# stepper-v1_1.net
KiCad netlist of a schematic drawn in EAGLE
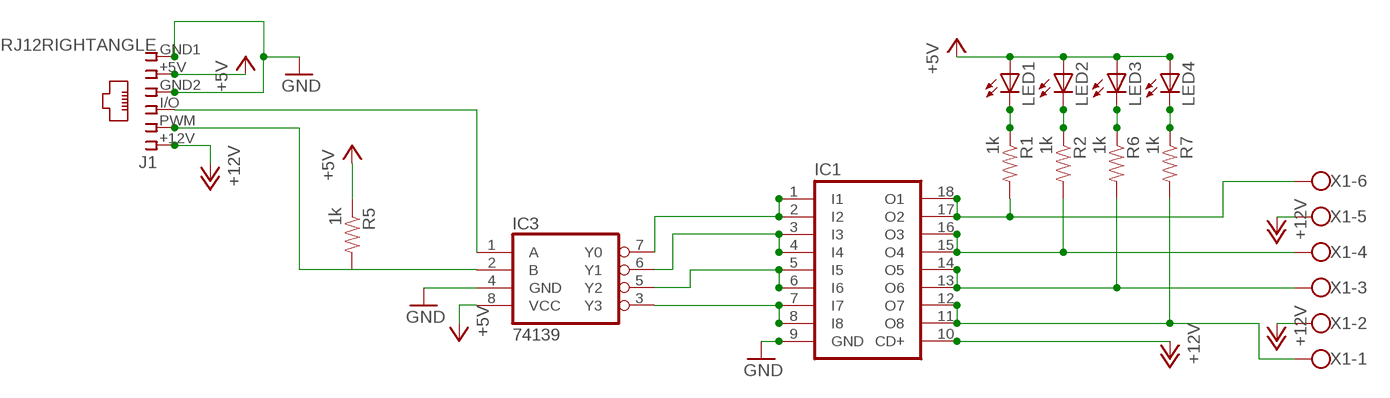
[diagram p0: schematic, sheet 1]

(export (version "E")
  (design (tool "Eeschema 10.0.6"))
  (components
    (comp (ref "IC1")
      (value "ULN2803A")
      (footprint "eagle-import:SO18W")
      (libsource (lib "eagle-import") (part "ULN2803A"))
    )
    (comp (ref "IC3")
      (value "74139")
      (footprint "eagle-import:SSOP08")
      (libsource (lib "eagle-import") (part "74139"))
    )
    (comp (ref "J1")
      (value "RJ12RIGHTANGLE")
      (footprint "eagle-import:RJ12-RIGHTANGLE")
      (libsource (lib "eagle-import") (part "RJ12RIGHTANGLE"))
    )
    (comp (ref "LED1")
      (value "LED3MM")
      (footprint "eagle-import:LED3MM")
      (libsource (lib "eagle-import") (part "LED3MM"))
    )
    (comp (ref "LED2")
      (value "LED3MM")
      (footprint "eagle-import:LED3MM")
      (libsource (lib "eagle-import") (part "LED3MM"))
    )
    (comp (ref "LED3")
      (value "LED3MM")
      (footprint "eagle-import:LED3MM")
      (libsource (lib "eagle-import") (part "LED3MM"))
    )
    (comp (ref "LED4")
      (value "LED3MM")
      (footprint "eagle-import:LED3MM")
      (libsource (lib "eagle-import") (part "LED3MM"))
    )
    (comp (ref "R1")
      (value "1k")
      (footprint "eagle-import:1206")
      (libsource (lib "eagle-import") (part "RESISTOR1206"))
    )
    (comp (ref "R2")
      (value "1k")
      (footprint "eagle-import:1206")
      (libsource (lib "eagle-import") (part "RESISTOR1206"))
    )
    (comp (ref "R5")
      (value "1k")
      (footprint "eagle-import:1206")
      (libsource (lib "eagle-import") (part "RESISTOR1206"))
    )
    (comp (ref "R6")
      (value "1k")
      (footprint "eagle-import:1206")
      (libsource (lib "eagle-import") (part "RESISTOR1206"))
    )
    (comp (ref "R7")
      (value "1k")
      (footprint "eagle-import:1206")
      (libsource (lib "eagle-import") (part "RESISTOR1206"))
    )
    (comp (ref "X1")
      (value "W237-6")
      (footprint "eagle-import:W237-6")
      (libsource (lib "eagle-import") (part "W237-6"))
    )
  )
  (nets
    (net (code "1") (name "+5V") (class "Default")
      (node (ref "IC3") (pin "8") (pinfunction "VCC_8") (pintype "power_in"))
      (node (ref "J1") (pin "+5V") (pinfunction "5_+5V") (pintype "bidirectional"))
      (node (ref "LED1") (pin "A") (pinfunction "A_A") (pintype "passive"))
      (node (ref "LED2") (pin "A") (pinfunction "A_A") (pintype "passive"))
      (node (ref "LED3") (pin "A") (pinfunction "A_A") (pintype "passive"))
      (node (ref "LED4") (pin "A") (pinfunction "A_A") (pintype "passive"))
      (node (ref "R5") (pin "1") (pinfunction "1_1") (pintype "passive"))
    )
    (net (code "2") (name "+12V") (class "Default")
      (node (ref "IC1") (pin "10") (pinfunction "CD+_10") (pintype "passive"))
      (node (ref "J1") (pin "+12V") (pinfunction "1_+12V") (pintype "bidirectional"))
      (node (ref "X1") (pin "2") (pinfunction "KL_2") (pintype "passive"))
      (node (ref "X1") (pin "5") (pinfunction "KL_5") (pintype "passive"))
    )
    (net (code "3") (name "GND") (class "Default")
      (node (ref "IC1") (pin "9") (pinfunction "GND_9") (pintype "power_in"))
      (node (ref "IC3") (pin "4") (pinfunction "GND_4") (pintype "power_in"))
      (node (ref "J1") (pin "GND1") (pinfunction "6_GND1") (pintype "bidirectional"))
      (node (ref "J1") (pin "GND2") (pinfunction "4_GND2") (pintype "bidirectional"))
    )
    (net (code "4") (name "Net-(IC1-I1)") (class "Default")
      (node (ref "IC1") (pin "1") (pinfunction "I1_1") (pintype "input"))
      (node (ref "IC1") (pin "2") (pinfunction "I2_2") (pintype "input"))
      (node (ref "IC3") (pin "7") (pinfunction "Y0_7") (pintype "output"))
    )
    (net (code "5") (name "Net-(IC1-I3)") (class "Default")
      (node (ref "IC1") (pin "3") (pinfunction "I3_3") (pintype "input"))
      (node (ref "IC1") (pin "4") (pinfunction "I4_4") (pintype "input"))
      (node (ref "IC3") (pin "6") (pinfunction "Y1_6") (pintype "output"))
    )
    (net (code "6") (name "Net-(IC1-I5)") (class "Default")
      (node (ref "IC1") (pin "5") (pinfunction "I5_5") (pintype "input"))
      (node (ref "IC1") (pin "6") (pinfunction "I6_6") (pintype "input"))
      (node (ref "IC3") (pin "5") (pinfunction "Y2_5") (pintype "output"))
    )
    (net (code "7") (name "Net-(IC1-I7)") (class "Default")
      (node (ref "IC1") (pin "7") (pinfunction "I7_7") (pintype "input"))
      (node (ref "IC1") (pin "8") (pinfunction "I8_8") (pintype "input"))
      (node (ref "IC3") (pin "3") (pinfunction "Y3_3") (pintype "output"))
    )
    (net (code "8") (name "Net-(IC1-O1)") (class "Default")
      (node (ref "IC1") (pin "17") (pinfunction "O2_17") (pintype "open_collector"))
      (node (ref "IC1") (pin "18") (pinfunction "O1_18") (pintype "open_collector"))
      (node (ref "R1") (pin "2") (pinfunction "2_2") (pintype "passive"))
      (node (ref "X1") (pin "6") (pinfunction "KL_6") (pintype "passive"))
    )
    (net (code "9") (name "Net-(IC1-O3)") (class "Default")
      (node (ref "IC1") (pin "15") (pinfunction "O4_15") (pintype "open_collector"))
      (node (ref "IC1") (pin "16") (pinfunction "O3_16") (pintype "open_collector"))
      (node (ref "R2") (pin "2") (pinfunction "2_2") (pintype "passive"))
      (node (ref "X1") (pin "4") (pinfunction "KL_4") (pintype "passive"))
    )
    (net (code "10") (name "Net-(IC1-O5)") (class "Default")
      (node (ref "IC1") (pin "13") (pinfunction "O6_13") (pintype "open_collector"))
      (node (ref "IC1") (pin "14") (pinfunction "O5_14") (pintype "open_collector"))
      (node (ref "R6") (pin "2") (pinfunction "2_2") (pintype "passive"))
      (node (ref "X1") (pin "3") (pinfunction "KL_3") (pintype "passive"))
    )
    (net (code "11") (name "Net-(IC1-O7)") (class "Default")
      (node (ref "IC1") (pin "11") (pinfunction "O8_11") (pintype "open_collector"))
      (node (ref "IC1") (pin "12") (pinfunction "O7_12") (pintype "open_collector"))
      (node (ref "R7") (pin "2") (pinfunction "2_2") (pintype "passive"))
      (node (ref "X1") (pin "1") (pinfunction "KL_1") (pintype "passive"))
    )
    (net (code "12") (name "Net-(IC3-A)") (class "Default")
      (node (ref "IC3") (pin "1") (pinfunction "A_1") (pintype "input"))
      (node (ref "J1") (pin "I/O") (pinfunction "3_I/O") (pintype "bidirectional"))
    )
    (net (code "13") (name "Net-(IC3-B)") (class "Default")
      (node (ref "IC3") (pin "2") (pinfunction "B_2") (pintype "input"))
      (node (ref "J1") (pin "PWM") (pinfunction "2_PWM") (pintype "bidirectional"))
      (node (ref "R5") (pin "2") (pinfunction "2_2") (pintype "passive"))
    )
    (net (code "14") (name "Net-(LED1-C)") (class "Default")
      (node (ref "LED1") (pin "K") (pinfunction "C_K") (pintype "passive"))
      (node (ref "R1") (pin "1") (pinfunction "1_1") (pintype "passive"))
    )
    (net (code "15") (name "Net-(LED2-C)") (class "Default")
      (node (ref "LED2") (pin "K") (pinfunction "C_K") (pintype "passive"))
      (node (ref "R2") (pin "1") (pinfunction "1_1") (pintype "passive"))
    )
    (net (code "16") (name "Net-(LED3-C)") (class "Default")
      (node (ref "LED3") (pin "K") (pinfunction "C_K") (pintype "passive"))
      (node (ref "R6") (pin "1") (pinfunction "1_1") (pintype "passive"))
    )
    (net (code "17") (name "Net-(LED4-C)") (class "Default")
      (node (ref "LED4") (pin "K") (pinfunction "C_K") (pintype "passive"))
      (node (ref "R7") (pin "1") (pinfunction "1_1") (pintype "passive"))
    )
  )
)
